# M707C.net
KiCad netlist of a schematic drawn in EAGLE
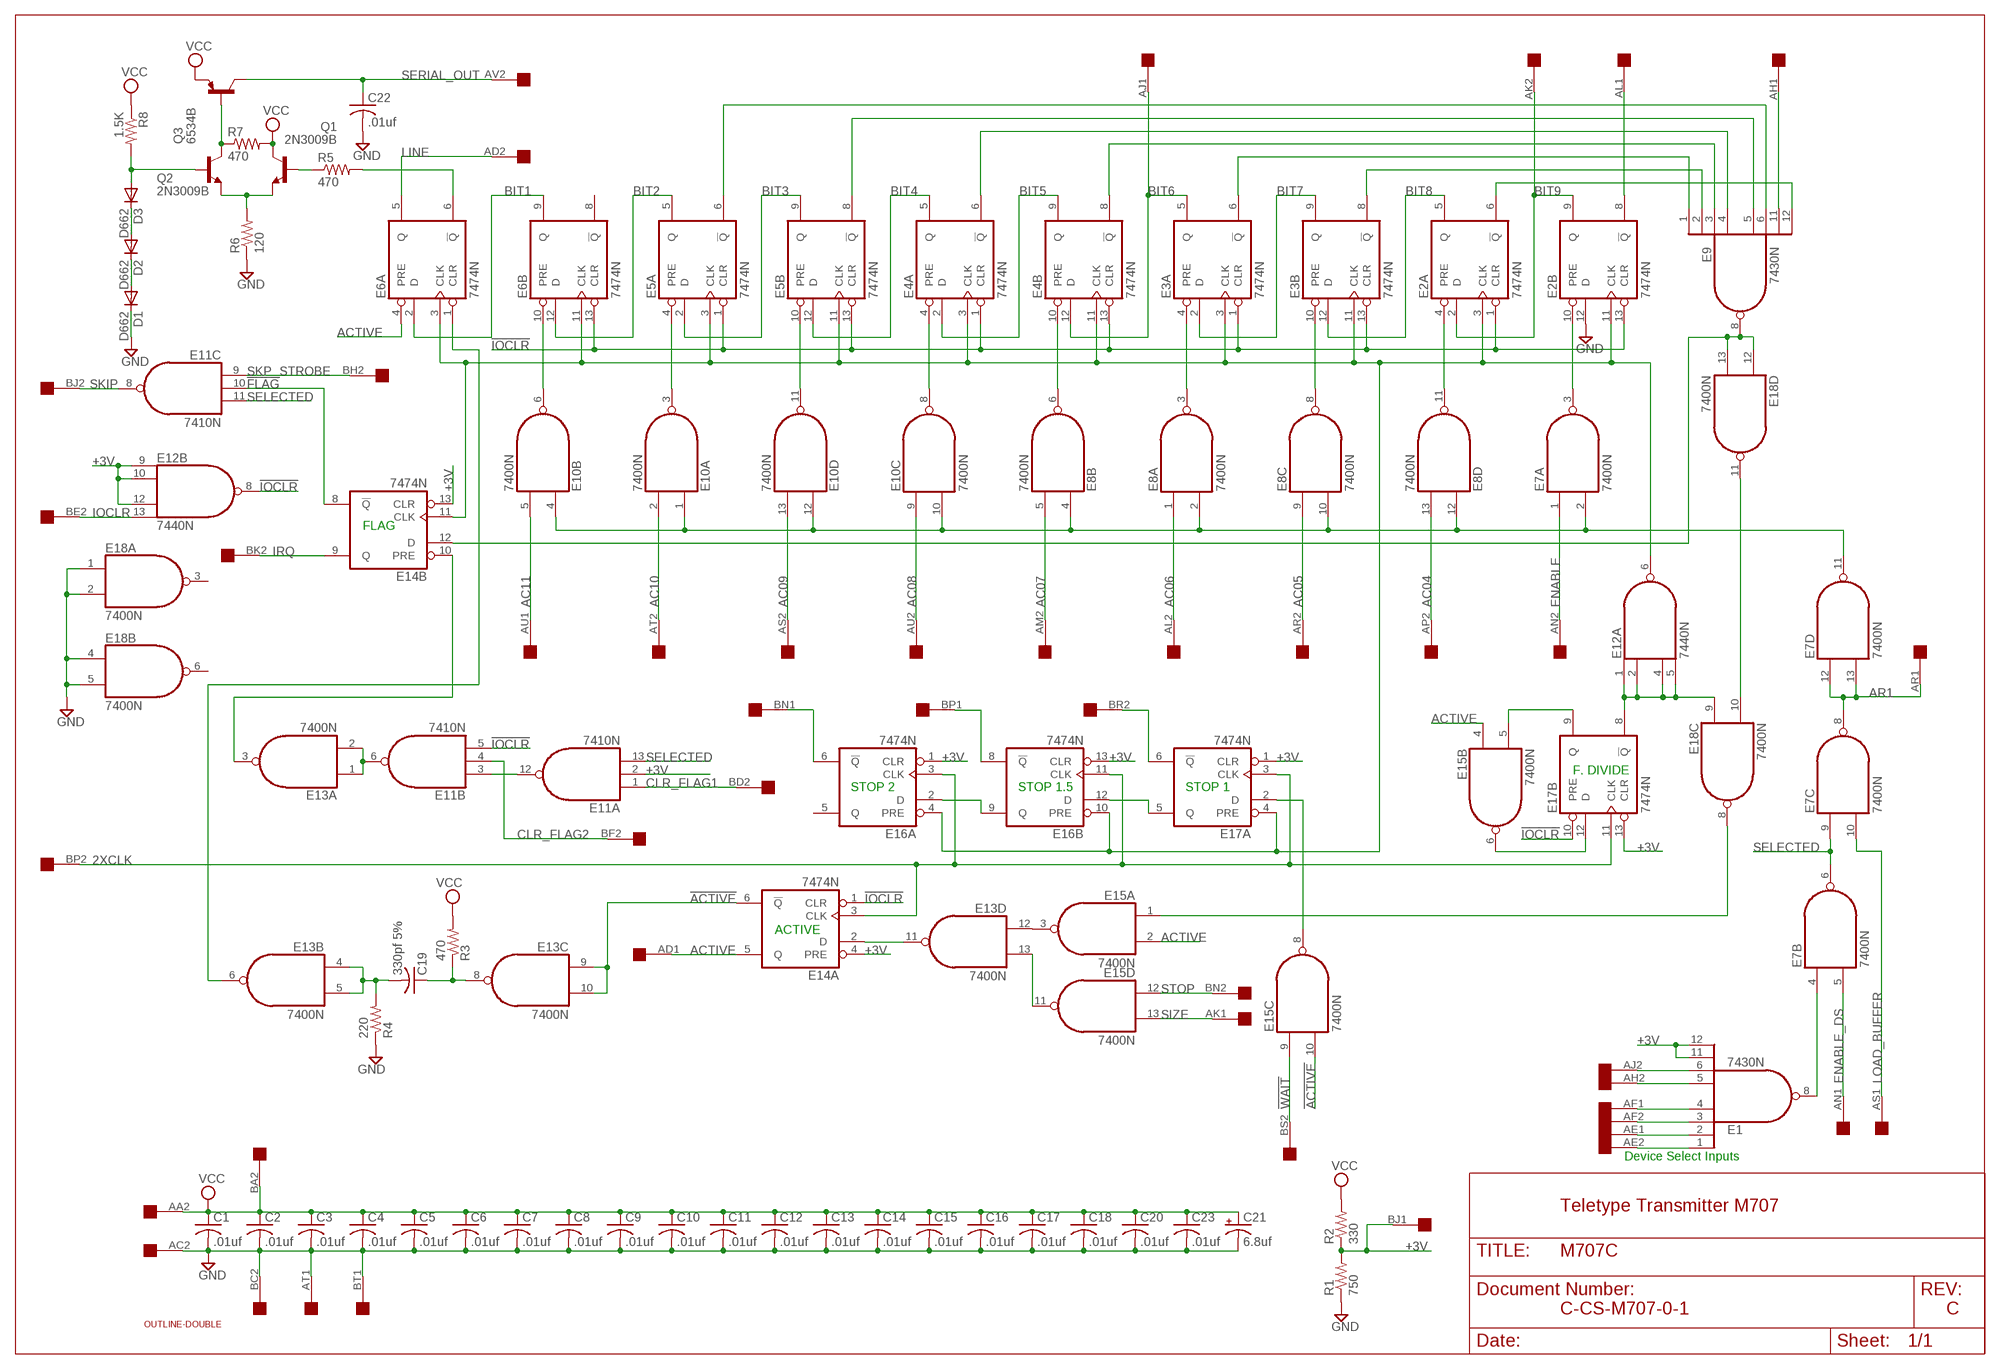
[diagram p0: schematic, sheet 1]

(export (version "E")
  (design (tool "Eeschema 10.0.6"))
  (components
    (comp (ref "C1")
      (value ".01uf")
      (footprint "eagle-import:C075-032X103")
      (libsource (lib "eagle-import") (part "C-US075-032X103"))
    )
    (comp (ref "C2")
      (value ".01uf")
      (footprint "eagle-import:C075-032X103")
      (libsource (lib "eagle-import") (part "C-US075-032X103"))
    )
    (comp (ref "C3")
      (value ".01uf")
      (footprint "eagle-import:C075-032X103")
      (libsource (lib "eagle-import") (part "C-US075-032X103"))
    )
    (comp (ref "C4")
      (value ".01uf")
      (footprint "eagle-import:C075-032X103")
      (libsource (lib "eagle-import") (part "C-US075-032X103"))
    )
    (comp (ref "C5")
      (value ".01uf")
      (footprint "eagle-import:C075-032X103")
      (libsource (lib "eagle-import") (part "C-US075-032X103"))
    )
    (comp (ref "C6")
      (value ".01uf")
      (footprint "eagle-import:C075-032X103")
      (libsource (lib "eagle-import") (part "C-US075-032X103"))
    )
    (comp (ref "C7")
      (value ".01uf")
      (footprint "eagle-import:C075-032X103")
      (libsource (lib "eagle-import") (part "C-US075-032X103"))
    )
    (comp (ref "C8")
      (value ".01uf")
      (footprint "eagle-import:C075-032X103")
      (libsource (lib "eagle-import") (part "C-US075-032X103"))
    )
    (comp (ref "C9")
      (value ".01uf")
      (footprint "eagle-import:C075-032X103")
      (libsource (lib "eagle-import") (part "C-US075-032X103"))
    )
    (comp (ref "C10")
      (value ".01uf")
      (footprint "eagle-import:C075-032X103")
      (libsource (lib "eagle-import") (part "C-US075-032X103"))
    )
    (comp (ref "C11")
      (value ".01uf")
      (footprint "eagle-import:C075-032X103")
      (libsource (lib "eagle-import") (part "C-US075-032X103"))
    )
    (comp (ref "C12")
      (value ".01uf")
      (footprint "eagle-import:C075-032X103")
      (libsource (lib "eagle-import") (part "C-US075-032X103"))
    )
    (comp (ref "C13")
      (value ".01uf")
      (footprint "eagle-import:C075-032X103")
      (libsource (lib "eagle-import") (part "C-US075-032X103"))
    )
    (comp (ref "C14")
      (value ".01uf")
      (footprint "eagle-import:C075-032X103")
      (libsource (lib "eagle-import") (part "C-US075-032X103"))
    )
    (comp (ref "C15")
      (value ".01uf")
      (footprint "eagle-import:C075-032X103")
      (libsource (lib "eagle-import") (part "C-US075-032X103"))
    )
    (comp (ref "C16")
      (value ".01uf")
      (footprint "eagle-import:C075-032X103")
      (libsource (lib "eagle-import") (part "C-US075-032X103"))
    )
    (comp (ref "C17")
      (value ".01uf")
      (footprint "eagle-import:C075-032X103")
      (libsource (lib "eagle-import") (part "C-US075-032X103"))
    )
    (comp (ref "C18")
      (value ".01uf")
      (footprint "eagle-import:C075-032X103")
      (libsource (lib "eagle-import") (part "C-US075-032X103"))
    )
    (comp (ref "C19")
      (value "330pf 5%")
      (footprint "eagle-import:C150-054X183")
      (libsource (lib "eagle-import") (part "C-US150-054X183"))
    )
    (comp (ref "C20")
      (value ".01uf")
      (footprint "eagle-import:C075-032X103")
      (libsource (lib "eagle-import") (part "C-US075-032X103"))
    )
    (comp (ref "C21")
      (value "6.8uf")
      (footprint "eagle-import:E15-5")
      (libsource (lib "eagle-import") (part "CPOL-USE15-5AXIAL"))
    )
    (comp (ref "C22")
      (value ".01uf")
      (footprint "eagle-import:C075-032X103")
      (libsource (lib "eagle-import") (part "C-US075-032X103"))
    )
    (comp (ref "C23")
      (value ".01uf")
      (footprint "eagle-import:C075-032X103")
      (libsource (lib "eagle-import") (part "C-US075-032X103"))
    )
    (comp (ref "D1")
      (value "D662")
      (footprint "eagle-import:SOD61B")
      (libsource (lib "eagle-import") (part "BY609"))
    )
    (comp (ref "D2")
      (value "D662")
      (footprint "eagle-import:SOD61B")
      (libsource (lib "eagle-import") (part "BY609"))
    )
    (comp (ref "D3")
      (value "D662")
      (footprint "eagle-import:SOD61B")
      (libsource (lib "eagle-import") (part "BY609"))
    )
    (comp (ref "E1")
      (value "7430N")
      (footprint "eagle-import:DIL14")
      (libsource (lib "eagle-import") (part "7430N"))
    )
    (comp (ref "E2")
      (value "7474N")
      (footprint "eagle-import:DIL14")
      (libsource (lib "eagle-import") (part "7474NS"))
    )
    (comp (ref "E3")
      (value "7474N")
      (footprint "eagle-import:DIL14")
      (libsource (lib "eagle-import") (part "7474NS"))
    )
    (comp (ref "E4")
      (value "7474N")
      (footprint "eagle-import:DIL14")
      (libsource (lib "eagle-import") (part "7474NS"))
    )
    (comp (ref "E5")
      (value "7474N")
      (footprint "eagle-import:DIL14")
      (libsource (lib "eagle-import") (part "7474NS"))
    )
    (comp (ref "E6")
      (value "7474N")
      (footprint "eagle-import:DIL14")
      (libsource (lib "eagle-import") (part "7474NS"))
    )
    (comp (ref "E7")
      (value "7400N")
      (footprint "eagle-import:DIL14")
      (libsource (lib "eagle-import") (part "7400N"))
    )
    (comp (ref "E8")
      (value "7400N")
      (footprint "eagle-import:DIL14")
      (libsource (lib "eagle-import") (part "7400N"))
    )
    (comp (ref "E9")
      (value "7430N")
      (footprint "eagle-import:DIL14")
      (libsource (lib "eagle-import") (part "7430N"))
    )
    (comp (ref "E10")
      (value "7400N")
      (footprint "eagle-import:DIL14")
      (libsource (lib "eagle-import") (part "7400N"))
    )
    (comp (ref "E11")
      (value "7410N")
      (footprint "eagle-import:DIL14")
      (libsource (lib "eagle-import") (part "7410N"))
    )
    (comp (ref "E12")
      (value "7440N")
      (footprint "eagle-import:DIL14")
      (libsource (lib "eagle-import") (part "7420NS"))
    )
    (comp (ref "E13")
      (value "7400N")
      (footprint "eagle-import:DIL14")
      (libsource (lib "eagle-import") (part "7400N"))
    )
    (comp (ref "E14")
      (value "7474N")
      (footprint "eagle-import:DIL14")
      (libsource (lib "eagle-import") (part "7474NS"))
    )
    (comp (ref "E15")
      (value "7400N")
      (footprint "eagle-import:DIL14")
      (libsource (lib "eagle-import") (part "7400N"))
    )
    (comp (ref "E16")
      (value "7474N")
      (footprint "eagle-import:DIL14")
      (libsource (lib "eagle-import") (part "7474NS"))
    )
    (comp (ref "E17")
      (value "7474N")
      (footprint "eagle-import:DIL14")
      (libsource (lib "eagle-import") (part "7474NS"))
    )
    (comp (ref "E18")
      (value "7400N")
      (footprint "eagle-import:DIL14")
      (libsource (lib "eagle-import") (part "7400N"))
    )
    (comp (ref "Q1")
      (value "2N3009B")
      (footprint "eagle-import:TO92-CBE")
      (libsource (lib "eagle-import") (part "-NPN-TO92-CBE2N4124"))
    )
    (comp (ref "Q2")
      (value "2N3009B")
      (footprint "eagle-import:TO92-CBE")
      (libsource (lib "eagle-import") (part "-NPN-TO92-CBE2N4124"))
    )
    (comp (ref "Q3")
      (value "6534B")
      (footprint "eagle-import:TO92-CBE")
      (libsource (lib "eagle-import") (part "-PNP-TO92-CBE2N4126"))
    )
    (comp (ref "R1")
      (value "750")
      (footprint "eagle-import:0207_15")
      (libsource (lib "eagle-import") (part "R-US_0207/15"))
    )
    (comp (ref "R2")
      (value "330")
      (footprint "eagle-import:0207_15")
      (libsource (lib "eagle-import") (part "R-US_0207/15"))
    )
    (comp (ref "R3")
      (value "470")
      (footprint "eagle-import:0207_10")
      (libsource (lib "eagle-import") (part "R-US_0207/10"))
    )
    (comp (ref "R4")
      (value "220")
      (footprint "eagle-import:0207_10")
      (libsource (lib "eagle-import") (part "R-US_0207/10"))
    )
    (comp (ref "R5")
      (value "470")
      (footprint "eagle-import:0207_10")
      (libsource (lib "eagle-import") (part "R-US_0207/10"))
    )
    (comp (ref "R6")
      (value "120")
      (footprint "eagle-import:0207_15")
      (libsource (lib "eagle-import") (part "R-US_0207/15"))
    )
    (comp (ref "R7")
      (value "470")
      (footprint "eagle-import:0207_10")
      (libsource (lib "eagle-import") (part "R-US_0207/10"))
    )
    (comp (ref "R8")
      (value "1.5K")
      (footprint "eagle-import:0207_15")
      (libsource (lib "eagle-import") (part "R-US_0207/15"))
    )
    (comp (ref "U$1")
      (value "OUTLINE-DOUBLE")
      (footprint "eagle-import:DOUBLE")
      (libsource (lib "eagle-import") (part "OUTLINE-DOUBLE"))
    )
    (comp (ref "U$2")
      (value "DOUBLE")
      (footprint "eagle-import:EDGE-CON4")
      (libsource (lib "eagle-import") (part "DOUBLE"))
    )
  )
  (nets
    (net (code "1") (name "/+3V") (class "Default")
      (node (ref "E1") (pin "11") (pinfunction "I6_11") (pintype "input"))
      (node (ref "E1") (pin "12") (pinfunction "I7_12") (pintype "input"))
      (node (ref "E11") (pin "2") (pinfunction "I1_2") (pintype "input"))
      (node (ref "E12") (pin "10") (pinfunction "I1_10") (pintype "input"))
      (node (ref "E12") (pin "12") (pinfunction "I2_12") (pintype "input"))
      (node (ref "E12") (pin "9") (pinfunction "I0_9") (pintype "input"))
      (node (ref "E14") (pin "13") (pinfunction "CLR_13") (pintype "input"))
      (node (ref "E14") (pin "4") (pinfunction "PRE_4") (pintype "input"))
      (node (ref "E16") (pin "1") (pinfunction "CLR_1") (pintype "input"))
      (node (ref "E16") (pin "13") (pinfunction "CLR_13") (pintype "input"))
      (node (ref "E17") (pin "1") (pinfunction "CLR_1") (pintype "input"))
      (node (ref "E17") (pin "13") (pinfunction "CLR_13") (pintype "input"))
      (node (ref "R1") (pin "2") (pinfunction "2_2") (pintype "passive"))
      (node (ref "R2") (pin "1") (pinfunction "1_1") (pintype "passive"))
      (node (ref "U$2") (pin "BJ1") (pinfunction "1_BJ1") (pintype "bidirectional"))
    )
    (net (code "2") (name "/2XCLK") (class "Default")
      (node (ref "E14") (pin "3") (pinfunction "CLK_3") (pintype "input"))
      (node (ref "E16") (pin "11") (pinfunction "CLK_11") (pintype "input"))
      (node (ref "E16") (pin "3") (pinfunction "CLK_3") (pintype "input"))
      (node (ref "E17") (pin "11") (pinfunction "CLK_11") (pintype "input"))
      (node (ref "E17") (pin "3") (pinfunction "CLK_3") (pintype "input"))
      (node (ref "U$2") (pin "BP2") (pinfunction "1_BP2") (pintype "bidirectional"))
    )
    (net (code "3") (name "/AC04") (class "Default")
      (node (ref "E8") (pin "13") (pinfunction "I1_13") (pintype "input"))
      (node (ref "U$2") (pin "AP2") (pinfunction "1_AP2") (pintype "bidirectional"))
    )
    (net (code "4") (name "/AC05") (class "Default")
      (node (ref "E8") (pin "9") (pinfunction "I0_9") (pintype "input"))
      (node (ref "U$2") (pin "AR2") (pinfunction "1_AR2") (pintype "bidirectional"))
    )
    (net (code "5") (name "/AC06") (class "Default")
      (node (ref "E8") (pin "1") (pinfunction "I0_1") (pintype "input"))
      (node (ref "U$2") (pin "AL2") (pinfunction "1_AL2") (pintype "bidirectional"))
    )
    (net (code "6") (name "/AC07") (class "Default")
      (node (ref "E8") (pin "5") (pinfunction "I1_5") (pintype "input"))
      (node (ref "U$2") (pin "AM2") (pinfunction "1_AM2") (pintype "bidirectional"))
    )
    (net (code "7") (name "/AC08") (class "Default")
      (node (ref "E10") (pin "9") (pinfunction "I0_9") (pintype "input"))
      (node (ref "U$2") (pin "AU2") (pinfunction "1_AU2") (pintype "bidirectional"))
    )
    (net (code "8") (name "/AC09") (class "Default")
      (node (ref "E10") (pin "13") (pinfunction "I1_13") (pintype "input"))
      (node (ref "U$2") (pin "AS2") (pinfunction "1_AS2") (pintype "bidirectional"))
    )
    (net (code "9") (name "/AC10") (class "Default")
      (node (ref "E10") (pin "2") (pinfunction "I1_2") (pintype "input"))
      (node (ref "U$2") (pin "AT2") (pinfunction "1_AT2") (pintype "bidirectional"))
    )
    (net (code "10") (name "/AC11") (class "Default")
      (node (ref "E10") (pin "5") (pinfunction "I1_5") (pintype "input"))
      (node (ref "U$2") (pin "AU1") (pinfunction "1_AU1") (pintype "bidirectional"))
    )
    (net (code "11") (name "/ACTIVE") (class "Default")
      (node (ref "E14") (pin "5") (pinfunction "Q_5") (pintype "output"))
      (node (ref "E15") (pin "2") (pinfunction "I1_2") (pintype "input"))
      (node (ref "E15") (pin "4") (pinfunction "I0_4") (pintype "input"))
      (node (ref "E6") (pin "4") (pinfunction "PRE_4") (pintype "input"))
      (node (ref "U$2") (pin "AD1") (pinfunction "1_AD1") (pintype "bidirectional"))
    )
    (net (code "12") (name "/AR1") (class "Default")
      (node (ref "E7") (pin "12") (pinfunction "I0_12") (pintype "input"))
      (node (ref "E7") (pin "13") (pinfunction "I1_13") (pintype "input"))
      (node (ref "E7") (pin "8") (pinfunction "O_8") (pintype "output"))
      (node (ref "U$2") (pin "AR1") (pinfunction "1_AR1") (pintype "bidirectional"))
    )
    (net (code "13") (name "/BIT1") (class "Default")
      (node (ref "E6") (pin "2") (pinfunction "D_2") (pintype "input"))
      (node (ref "E6") (pin "9") (pinfunction "Q_9") (pintype "output"))
    )
    (net (code "14") (name "/BIT2") (class "Default")
      (node (ref "E5") (pin "5") (pinfunction "Q_5") (pintype "output"))
      (node (ref "E6") (pin "12") (pinfunction "D_12") (pintype "input"))
    )
    (net (code "15") (name "/BIT3") (class "Default")
      (node (ref "E5") (pin "2") (pinfunction "D_2") (pintype "input"))
      (node (ref "E5") (pin "9") (pinfunction "Q_9") (pintype "output"))
    )
    (net (code "16") (name "/BIT4") (class "Default")
      (node (ref "E4") (pin "5") (pinfunction "Q_5") (pintype "output"))
      (node (ref "E5") (pin "12") (pinfunction "D_12") (pintype "input"))
    )
    (net (code "17") (name "/BIT5") (class "Default")
      (node (ref "E4") (pin "2") (pinfunction "D_2") (pintype "input"))
      (node (ref "E4") (pin "9") (pinfunction "Q_9") (pintype "output"))
    )
    (net (code "18") (name "/BIT6") (class "Default")
      (node (ref "E3") (pin "5") (pinfunction "Q_5") (pintype "output"))
      (node (ref "E4") (pin "12") (pinfunction "D_12") (pintype "input"))
      (node (ref "U$2") (pin "AJ1") (pinfunction "1_AJ1") (pintype "bidirectional"))
    )
    (net (code "19") (name "/BIT7") (class "Default")
      (node (ref "E3") (pin "2") (pinfunction "D_2") (pintype "input"))
      (node (ref "E3") (pin "9") (pinfunction "Q_9") (pintype "output"))
    )
    (net (code "20") (name "/BIT8") (class "Default")
      (node (ref "E2") (pin "5") (pinfunction "Q_5") (pintype "output"))
      (node (ref "E3") (pin "12") (pinfunction "D_12") (pintype "input"))
    )
    (net (code "21") (name "/BIT9") (class "Default")
      (node (ref "E2") (pin "2") (pinfunction "D_2") (pintype "input"))
      (node (ref "E2") (pin "9") (pinfunction "Q_9") (pintype "output"))
      (node (ref "U$2") (pin "AK2") (pinfunction "1_AK2") (pintype "bidirectional"))
    )
    (net (code "22") (name "/CLR_FLAG1") (class "Default")
      (node (ref "E11") (pin "1") (pinfunction "I0_1") (pintype "input"))
      (node (ref "U$2") (pin "BD2") (pinfunction "1_BD2") (pintype "bidirectional"))
    )
    (net (code "23") (name "/CLR_FLAG2") (class "Default")
      (node (ref "E11") (pin "4") (pinfunction "I1_4") (pintype "input"))
      (node (ref "U$2") (pin "BF2") (pinfunction "1_BF2") (pintype "bidirectional"))
    )
    (net (code "24") (name "/ENABLE") (class "Default")
      (node (ref "E7") (pin "1") (pinfunction "I0_1") (pintype "input"))
      (node (ref "U$2") (pin "AN2") (pinfunction "1_AN2") (pintype "bidirectional"))
    )
    (net (code "25") (name "/ENABLE_DS") (class "Default")
      (node (ref "E7") (pin "5") (pinfunction "I1_5") (pintype "input"))
      (node (ref "U$2") (pin "AN1") (pinfunction "1_AN1") (pintype "bidirectional"))
    )
    (net (code "26") (name "/IOCLR") (class "Default")
      (node (ref "E12") (pin "13") (pinfunction "I3_13") (pintype "input"))
      (node (ref "U$2") (pin "BE2") (pinfunction "1_BE2") (pintype "bidirectional"))
    )
    (net (code "27") (name "/IRQ") (class "Default")
      (node (ref "E14") (pin "9") (pinfunction "Q_9") (pintype "output"))
      (node (ref "U$2") (pin "BK2") (pinfunction "1_BK2") (pintype "bidirectional"))
    )
    (net (code "28") (name "/LINE") (class "Default")
      (node (ref "E6") (pin "5") (pinfunction "Q_5") (pintype "output"))
      (node (ref "U$2") (pin "AD2") (pinfunction "1_AD2") (pintype "bidirectional"))
    )
    (net (code "29") (name "/LOAD_BUFFER") (class "Default")
      (node (ref "E7") (pin "10") (pinfunction "I1_10") (pintype "input"))
      (node (ref "U$2") (pin "AS1") (pinfunction "1_AS1") (pintype "bidirectional"))
    )
    (net (code "30") (name "/SELECTED") (class "Default")
      (node (ref "E11") (pin "11") (pinfunction "I2_11") (pintype "input"))
      (node (ref "E11") (pin "13") (pinfunction "I2_13") (pintype "input"))
      (node (ref "E7") (pin "6") (pinfunction "O_6") (pintype "output"))
      (node (ref "E7") (pin "9") (pinfunction "I0_9") (pintype "input"))
    )
    (net (code "31") (name "/SERIAL_OUT") (class "Default")
      (node (ref "C22") (pin "1") (pinfunction "1_1") (pintype "passive"))
      (node (ref "Q3") (pin "C") (pinfunction "C_C") (pintype "passive"))
      (node (ref "U$2") (pin "AV2") (pinfunction "1_AV2") (pintype "bidirectional"))
    )
    (net (code "32") (name "/SIZE") (class "Default")
      (node (ref "E15") (pin "13") (pinfunction "I1_13") (pintype "input"))
      (node (ref "U$2") (pin "AK1") (pinfunction "1_AK1") (pintype "bidirectional"))
    )
    (net (code "33") (name "/SKIP") (class "Default")
      (node (ref "E11") (pin "8") (pinfunction "O_8") (pintype "output"))
      (node (ref "U$2") (pin "BJ2") (pinfunction "1_BJ2") (pintype "bidirectional"))
    )
    (net (code "34") (name "/SKP_STROBE") (class "Default")
      (node (ref "E11") (pin "9") (pinfunction "I0_9") (pintype "input"))
      (node (ref "U$2") (pin "BH2") (pinfunction "1_BH2") (pintype "bidirectional"))
    )
    (net (code "35") (name "/STOP") (class "Default")
      (node (ref "E15") (pin "12") (pinfunction "I0_12") (pintype "input"))
      (node (ref "U$2") (pin "BN2") (pinfunction "1_BN2") (pintype "bidirectional"))
    )
    (net (code "36") (name "/~{ACTIVE}") (class "Default")
      (node (ref "E13") (pin "10") (pinfunction "I1_10") (pintype "input"))
      (node (ref "E13") (pin "9") (pinfunction "I0_9") (pintype "input"))
      (node (ref "E14") (pin "6") (pinfunction "~{Q}_6") (pintype "output"))
      (node (ref "E15") (pin "10") (pinfunction "I1_10") (pintype "input"))
    )
    (net (code "37") (name "/~{FLAG}") (class "Default")
      (node (ref "E11") (pin "10") (pinfunction "I1_10") (pintype "input"))
      (node (ref "E14") (pin "8") (pinfunction "~{Q}_8") (pintype "output"))
    )
    (net (code "38") (name "/~{IOCLR}") (class "Default")
      (node (ref "E11") (pin "5") (pinfunction "I2_5") (pintype "input"))
      (node (ref "E12") (pin "8") (pinfunction "O_8") (pintype "output"))
      (node (ref "E14") (pin "1") (pinfunction "CLR_1") (pintype "input"))
      (node (ref "E17") (pin "10") (pinfunction "PRE_10") (pintype "input"))
      (node (ref "E2") (pin "1") (pinfunction "CLR_1") (pintype "input"))
      (node (ref "E2") (pin "13") (pinfunction "CLR_13") (pintype "input"))
      (node (ref "E3") (pin "1") (pinfunction "CLR_1") (pintype "input"))
      (node (ref "E3") (pin "13") (pinfunction "CLR_13") (pintype "input"))
      (node (ref "E4") (pin "1") (pinfunction "CLR_1") (pintype "input"))
      (node (ref "E4") (pin "13") (pinfunction "CLR_13") (pintype "input"))
      (node (ref "E5") (pin "1") (pinfunction "CLR_1") (pintype "input"))
      (node (ref "E5") (pin "13") (pinfunction "CLR_13") (pintype "input"))
      (node (ref "E6") (pin "13") (pinfunction "CLR_13") (pintype "input"))
    )
    (net (code "39") (name "/~{WAIT}") (class "Default")
      (node (ref "E15") (pin "9") (pinfunction "I0_9") (pintype "input"))
      (node (ref "U$2") (pin "BS2") (pinfunction "1_BS2") (pintype "bidirectional"))
    )
    (net (code "40") (name "GND") (class "Default")
      (node (ref "C1") (pin "2") (pinfunction "2_2") (pintype "passive"))
      (node (ref "C10") (pin "2") (pinfunction "2_2") (pintype "passive"))
      (node (ref "C11") (pin "2") (pinfunction "2_2") (pintype "passive"))
      (node (ref "C12") (pin "2") (pinfunction "2_2") (pintype "passive"))
      (node (ref "C13") (pin "2") (pinfunction "2_2") (pintype "passive"))
      (node (ref "C14") (pin "2") (pinfunction "2_2") (pintype "passive"))
      (node (ref "C15") (pin "2") (pinfunction "2_2") (pintype "passive"))
      (node (ref "C16") (pin "2") (pinfunction "2_2") (pintype "passive"))
      (node (ref "C17") (pin "2") (pinfunction "2_2") (pintype "passive"))
      (node (ref "C18") (pin "2") (pinfunction "2_2") (pintype "passive"))
      (node (ref "C2") (pin "2") (pinfunction "2_2") (pintype "passive"))
      (node (ref "C20") (pin "2") (pinfunction "2_2") (pintype "passive"))
      (node (ref "C21") (pin "-") (pinfunction "-_-") (pintype "passive"))
      (node (ref "C22") (pin "2") (pinfunction "2_2") (pintype "passive"))
      (node (ref "C23") (pin "2") (pinfunction "2_2") (pintype "passive"))
      (node (ref "C3") (pin "2") (pinfunction "2_2") (pintype "passive"))
      (node (ref "C4") (pin "2") (pinfunction "2_2") (pintype "passive"))
      (node (ref "C5") (pin "2") (pinfunction "2_2") (pintype "passive"))
      (node (ref "C6") (pin "2") (pinfunction "2_2") (pintype "passive"))
      (node (ref "C7") (pin "2") (pinfunction "2_2") (pintype "passive"))
      (node (ref "C8") (pin "2") (pinfunction "2_2") (pintype "passive"))
      (node (ref "C9") (pin "2") (pinfunction "2_2") (pintype "passive"))
      (node (ref "D1") (pin "C") (pinfunction "C_C") (pintype "passive"))
      (node (ref "E18") (pin "1") (pinfunction "I0_1") (pintype "input"))
      (node (ref "E18") (pin "2") (pinfunction "I1_2") (pintype "input"))
      (node (ref "E18") (pin "4") (pinfunction "I0_4") (pintype "input"))
      (node (ref "E18") (pin "5") (pinfunction "I1_5") (pintype "input"))
      (node (ref "E2") (pin "12") (pinfunction "D_12") (pintype "input"))
      (node (ref "R1") (pin "1") (pinfunction "1_1") (pintype "passive"))
      (node (ref "R4") (pin "1") (pinfunction "1_1") (pintype "passive"))
      (node (ref "R6") (pin "1") (pinfunction "1_1") (pintype "passive"))
      (node (ref "U$2") (pin "AC2") (pinfunction "1_AC2") (pintype "bidirectional"))
      (node (ref "U$2") (pin "AT1") (pinfunction "1_AT1") (pintype "bidirectional"))
      (node (ref "U$2") (pin "BC2") (pinfunction "1_BC2") (pintype "bidirectional"))
      (node (ref "U$2") (pin "BT1") (pinfunction "1_BT1") (pintype "bidirectional"))
    )
    (net (code "41") (name "Net-(D1-PadA)") (class "Default")
      (node (ref "D1") (pin "A") (pinfunction "A_A") (pintype "passive"))
      (node (ref "D2") (pin "C") (pinfunction "C_C") (pintype "passive"))
    )
    (net (code "42") (name "Net-(D2-PadA)") (class "Default")
      (node (ref "D2") (pin "A") (pinfunction "A_A") (pintype "passive"))
      (node (ref "D3") (pin "C") (pinfunction "C_C") (pintype "passive"))
    )
    (net (code "43") (name "Net-(D3-PadA)") (class "Default")
      (node (ref "D3") (pin "A") (pinfunction "A_A") (pintype "passive"))
      (node (ref "Q2") (pin "B") (pinfunction "B_B") (pintype "passive"))
      (node (ref "R8") (pin "2") (pinfunction "2_2") (pintype "passive"))
    )
    (net (code "44") (name "Net-(E1A-I0)") (class "Default")
      (node (ref "E1") (pin "1") (pinfunction "I0_1") (pintype "input"))
      (node (ref "U$2") (pin "AE2") (pinfunction "1_AE2") (pintype "bidirectional"))
    )
    (net (code "45") (name "Net-(E1A-I1)") (class "Default")
      (node (ref "E1") (pin "2") (pinfunction "I1_2") (pintype "input"))
      (node (ref "U$2") (pin "AE1") (pinfunction "1_AE1") (pintype "bidirectional"))
    )
    (net (code "46") (name "Net-(E1A-I2)") (class "Default")
      (node (ref "E1") (pin "3") (pinfunction "I2_3") (pintype "input"))
      (node (ref "U$2") (pin "AF2") (pinfunction "1_AF2") (pintype "bidirectional"))
    )
    (net (code "47") (name "Net-(E1A-I3)") (class "Default")
      (node (ref "E1") (pin "4") (pinfunction "I3_4") (pintype "input"))
      (node (ref "U$2") (pin "AF1") (pinfunction "1_AF1") (pintype "bidirectional"))
    )
    (net (code "48") (name "Net-(E1A-I4)") (class "Default")
      (node (ref "E1") (pin "5") (pinfunction "I4_5") (pintype "input"))
      (node (ref "U$2") (pin "AH2") (pinfunction "1_AH2") (pintype "bidirectional"))
    )
    (net (code "49") (name "Net-(E1A-I5)") (class "Default")
      (node (ref "E1") (pin "6") (pinfunction "I5_6") (pintype "input"))
      (node (ref "U$2") (pin "AJ2") (pinfunction "1_AJ2") (pintype "bidirectional"))
    )
    (net (code "50") (name "Net-(E1A-O)") (class "Default")
      (node (ref "E1") (pin "8") (pinfunction "O_8") (pintype "output"))
      (node (ref "E7") (pin "4") (pinfunction "I0_4") (pintype "input"))
    )
    (net (code "51") (name "Net-(E2A-PRE)") (class "Default")
      (node (ref "E2") (pin "4") (pinfunction "PRE_4") (pintype "input"))
      (node (ref "E8") (pin "11") (pinfunction "O_11") (pintype "output"))
    )
    (net (code "52") (name "Net-(E2A-~{Q})") (class "Default")
      (node (ref "E2") (pin "6") (pinfunction "~{Q}_6") (pintype "output"))
      (node (ref "E9") (pin "12") (pinfunction "I7_12") (pintype "input"))
    )
    (net (code "53") (name "Net-(E2B-PRE)") (class "Default")
      (node (ref "E2") (pin "10") (pinfunction "PRE_10") (pintype "input"))
      (node (ref "E7") (pin "3") (pinfunction "O_3") (pintype "output"))
    )
    (net (code "54") (name "Net-(E2B-~{Q})") (class "Default")
      (node (ref "E2") (pin "8") (pinfunction "~{Q}_8") (pintype "output"))
      (node (ref "U$2") (pin "AL1") (pinfunction "1_AL1") (pintype "bidirectional"))
    )
    (net (code "55") (name "Net-(E3A-PRE)") (class "Default")
      (node (ref "E3") (pin "4") (pinfunction "PRE_4") (pintype "input"))
      (node (ref "E8") (pin "3") (pinfunction "O_3") (pintype "output"))
    )
    (net (code "56") (name "Net-(E3A-~{Q})") (class "Default")
      (node (ref "E3") (pin "6") (pinfunction "~{Q}_6") (pintype "output"))
      (node (ref "E9") (pin "1") (pinfunction "I0_1") (pintype "input"))
    )
    (net (code "57") (name "Net-(E3B-PRE)") (class "Default")
      (node (ref "E3") (pin "10") (pinfunction "PRE_10") (pintype "input"))
      (node (ref "E8") (pin "8") (pinfunction "O_8") (pintype "output"))
    )
    (net (code "58") (name "Net-(E3B-~{Q})") (class "Default")
      (node (ref "E3") (pin "8") (pinfunction "~{Q}_8") (pintype "output"))
      (node (ref "E9") (pin "2") (pinfunction "I1_2") (pintype "input"))
    )
    (net (code "59") (name "Net-(E4A-~{Q})") (class "Default")
      (node (ref "E4") (pin "6") (pinfunction "~{Q}_6") (pintype "output"))
      (node (ref "E9") (pin "4") (pinfunction "I3_4") (pintype "input"))
    )
    (net (code "60") (name "Net-(E4B-PRE)") (class "Default")
      (node (ref "E4") (pin "10") (pinfunction "PRE_10") (pintype "input"))
      (node (ref "E8") (pin "6") (pinfunction "O_6") (pintype "output"))
    )
    (net (code "61") (name "Net-(E4B-~{Q})") (class "Default")
      (node (ref "E4") (pin "8") (pinfunction "~{Q}_8") (pintype "output"))
      (node (ref "E9") (pin "3") (pinfunction "I2_3") (pintype "input"))
    )
    (net (code "62") (name "Net-(E5A-~{Q})") (class "Default")
      (node (ref "E5") (pin "6") (pinfunction "~{Q}_6") (pintype "output"))
      (node (ref "E9") (pin "6") (pinfunction "I5_6") (pintype "input"))
    )
    (net (code "63") (name "Net-(E5B-~{Q})") (class "Default")
      (node (ref "E5") (pin "8") (pinfunction "~{Q}_8") (pintype "output"))
      (node (ref "E9") (pin "5") (pinfunction "I4_5") (pintype "input"))
    )
    (net (code "64") (name "Net-(E6A-~{Q})") (class "Default")
      (node (ref "E6") (pin "6") (pinfunction "~{Q}_6") (pintype "output"))
      (node (ref "R5") (pin "2") (pinfunction "2_2") (pintype "passive"))
    )
    (net (code "65") (name "Net-(E9A-I6)") (class "Default")
      (node (ref "E9") (pin "11") (pinfunction "I6_11") (pintype "input"))
      (node (ref "U$2") (pin "AH1") (pinfunction "1_AH1") (pintype "bidirectional"))
    )
    (net (code "66") (name "Net-(E10A-I0)") (class "Default")
      (node (ref "E10") (pin "1") (pinfunction "I0_1") (pintype "input"))
      (node (ref "E10") (pin "10") (pinfunction "I1_10") (pintype "input"))
      (node (ref "E10") (pin "12") (pinfunction "I0_12") (pintype "input"))
      (node (ref "E10") (pin "4") (pinfunction "I0_4") (pintype "input"))
      (node (ref "E7") (pin "11") (pinfunction "O_11") (pintype "output"))
      (node (ref "E7") (pin "2") (pinfunction "I1_2") (pintype "input"))
      (node (ref "E8") (pin "10") (pinfunction "I1_10") (pintype "input"))
      (node (ref "E8") (pin "12") (pinfunction "I0_12") (pintype "input"))
      (node (ref "E8") (pin "2") (pinfunction "I1_2") (pintype "input"))
      (node (ref "E8") (pin "4") (pinfunction "I0_4") (pintype "input"))
    )
    (net (code "67") (name "Net-(E10A-O)") (class "Default")
      (node (ref "E10") (pin "3") (pinfunction "O_3") (pintype "output"))
      (node (ref "E5") (pin "4") (pinfunction "PRE_4") (pintype "input"))
    )
    (net (code "68") (name "Net-(E10B-O)") (class "Default")
      (node (ref "E10") (pin "6") (pinfunction "O_6") (pintype "output"))
      (node (ref "E6") (pin "10") (pinfunction "PRE_10") (pintype "input"))
    )
    (net (code "69") (name "Net-(E10C-O)") (class "Default")
      (node (ref "E10") (pin "8") (pinfunction "O_8") (pintype "output"))
      (node (ref "E4") (pin "4") (pinfunction "PRE_4") (pintype "input"))
    )
    (net (code "70") (name "Net-(E10D-O)") (class "Default")
      (node (ref "E10") (pin "11") (pinfunction "O_11") (pintype "output"))
      (node (ref "E5") (pin "10") (pinfunction "PRE_10") (pintype "input"))
    )
    (net (code "71") (name "Net-(E11A-O)") (class "Default")
      (node (ref "E11") (pin "12") (pinfunction "O_12") (pintype "output"))
      (node (ref "E11") (pin "3") (pinfunction "I0_3") (pintype "input"))
    )
    (net (code "72") (name "Net-(E11B-O)") (class "Default")
      (node (ref "E11") (pin "6") (pinfunction "O_6") (pintype "output"))
      (node (ref "E13") (pin "1") (pinfunction "I0_1") (pintype "input"))
      (node (ref "E13") (pin "2") (pinfunction "I1_2") (pintype "input"))
    )
    (net (code "73") (name "Net-(E12A-I0)") (class "Default")
      (node (ref "E12") (pin "1") (pinfunction "I0_1") (pintype "input"))
      (node (ref "E12") (pin "2") (pinfunction "I1_2") (pintype "input"))
      (node (ref "E12") (pin "4") (pinfunction "I2_4") (pintype "input"))
      (node (ref "E12") (pin "5") (pinfunction "I3_5") (pintype "input"))
      (node (ref "E17") (pin "8") (pinfunction "~{Q}_8") (pintype "output"))
      (node (ref "E18") (pin "9") (pinfunction "I0_9") (pintype "input"))
    )
    (net (code "74") (name "Net-(E12A-O)") (class "Default")
      (node (ref "E12") (pin "6") (pinfunction "O_6") (pintype "output"))
      (node (ref "E14") (pin "11") (pinfunction "CLK_11") (pintype "input"))
      (node (ref "E16") (pin "10") (pinfunction "PRE_10") (pintype "input"))
      (node (ref "E16") (pin "4") (pinfunction "PRE_4") (pintype "input"))
      (node (ref "E17") (pin "4") (pinfunction "PRE_4") (pintype "input"))
      (node (ref "E2") (pin "11") (pinfunction "CLK_11") (pintype "input"))
      (node (ref "E2") (pin "3") (pinfunction "CLK_3") (pintype "input"))
      (node (ref "E3") (pin "11") (pinfunction "CLK_11") (pintype "input"))
      (node (ref "E3") (pin "3") (pinfunction "CLK_3") (pintype "input"))
      (node (ref "E4") (pin "11") (pinfunction "CLK_11") (pintype "input"))
      (node (ref "E4") (pin "3") (pinfunction "CLK_3") (pintype "input"))
      (node (ref "E5") (pin "11") (pinfunction "CLK_11") (pintype "input"))
      (node (ref "E5") (pin "3") (pinfunction "CLK_3") (pintype "input"))
      (node (ref "E6") (pin "11") (pinfunction "CLK_11") (pintype "input"))
      (node (ref "E6") (pin "3") (pinfunction "CLK_3") (pintype "input"))
    )
    (net (code "75") (name "Net-(E13A-O)") (class "Default")
      (node (ref "E13") (pin "3") (pinfunction "O_3") (pintype "output"))
      (node (ref "E14") (pin "10") (pinfunction "PRE_10") (pintype "input"))
    )
    (net (code "76") (name "Net-(E13B-I0)") (class "Default")
      (node (ref "C19") (pin "2") (pinfunction "2_2") (pintype "passive"))
      (node (ref "E13") (pin "4") (pinfunction "I0_4") (pintype "input"))
      (node (ref "E13") (pin "5") (pinfunction "I1_5") (pintype "input"))
      (node (ref "R4") (pin "2") (pinfunction "2_2") (pintype "passive"))
    )
    (net (code "77") (name "Net-(E13B-O)") (class "Default")
      (node (ref "E13") (pin "6") (pinfunction "O_6") (pintype "output"))
      (node (ref "E6") (pin "1") (pinfunction "CLR_1") (pintype "input"))
    )
    (net (code "78") (name "Net-(E13C-O)") (class "Default")
      (node (ref "C19") (pin "1") (pinfunction "1_1") (pintype "passive"))
      (node (ref "E13") (pin "8") (pinfunction "O_8") (pintype "output"))
      (node (ref "R3") (pin "1") (pinfunction "1_1") (pintype "passive"))
    )
    (net (code "79") (name "Net-(E13D-I0)") (class "Default")
      (node (ref "E13") (pin "12") (pinfunction "I0_12") (pintype "input"))
      (node (ref "E15") (pin "3") (pinfunction "O_3") (pintype "output"))
    )
    (net (code "80") (name "Net-(E13D-I1)") (class "Default")
      (node (ref "E13") (pin "13") (pinfunction "I1_13") (pintype "input"))
      (node (ref "E15") (pin "11") (pinfunction "O_11") (pintype "output"))
    )
    (net (code "81") (name "Net-(E13D-O)") (class "Default")
      (node (ref "E13") (pin "11") (pinfunction "O_11") (pintype "output"))
      (node (ref "E14") (pin "2") (pinfunction "D_2") (pintype "input"))
    )
    (net (code "82") (name "Net-(E14B-D)") (class "Default")
      (node (ref "E14") (pin "12") (pinfunction "D_12") (pintype "input"))
      (node (ref "E18") (pin "12") (pinfunction "I0_12") (pintype "input"))
      (node (ref "E18") (pin "13") (pinfunction "I1_13") (pintype "input"))
      (node (ref "E9") (pin "8") (pinfunction "O_8") (pintype "output"))
    )
    (net (code "83") (name "Net-(E15A-I0)") (class "Default")
      (node (ref "E15") (pin "1") (pinfunction "I0_1") (pintype "input"))
      (node (ref "E18") (pin "8") (pinfunction "O_8") (pintype "output"))
    )
    (net (code "84") (name "Net-(E15B-I1)") (class "Default")
      (node (ref "E15") (pin "5") (pinfunction "I1_5") (pintype "input"))
      (node (ref "E17") (pin "9") (pinfunction "Q_9") (pintype "output"))
    )
    (net (code "85") (name "Net-(E15B-O)") (class "Default")
      (node (ref "E15") (pin "6") (pinfunction "O_6") (pintype "output"))
      (node (ref "E17") (pin "12") (pinfunction "D_12") (pintype "input"))
    )
    (net (code "86") (name "Net-(E15C-O)") (class "Default")
      (node (ref "E15") (pin "8") (pinfunction "O_8") (pintype "output"))
      (node (ref "E17") (pin "2") (pinfunction "D_2") (pintype "input"))
    )
    (net (code "87") (name "Net-(E16A-D)") (class "Default")
      (node (ref "E16") (pin "2") (pinfunction "D_2") (pintype "input"))
      (node (ref "E16") (pin "9") (pinfunction "Q_9") (pintype "output"))
    )
    (net (code "88") (name "Net-(E16A-~{Q})") (class "Default")
      (node (ref "E16") (pin "6") (pinfunction "~{Q}_6") (pintype "output"))
      (node (ref "U$2") (pin "BN1") (pinfunction "1_BN1") (pintype "bidirectional"))
    )
    (net (code "89") (name "Net-(E16B-D)") (class "Default")
      (node (ref "E16") (pin "12") (pinfunction "D_12") (pintype "input"))
      (node (ref "E17") (pin "5") (pinfunction "Q_5") (pintype "output"))
    )
    (net (code "90") (name "Net-(E16B-~{Q})") (class "Default")
      (node (ref "E16") (pin "8") (pinfunction "~{Q}_8") (pintype "output"))
      (node (ref "U$2") (pin "BP1") (pinfunction "1_BP1") (pintype "bidirectional"))
    )
    (net (code "91") (name "Net-(E17A-~{Q})") (class "Default")
      (node (ref "E17") (pin "6") (pinfunction "~{Q}_6") (pintype "output"))
      (node (ref "U$2") (pin "BR2") (pinfunction "1_BR2") (pintype "bidirectional"))
    )
    (net (code "92") (name "Net-(E18C-I1)") (class "Default")
      (node (ref "E18") (pin "10") (pinfunction "I1_10") (pintype "input"))
      (node (ref "E18") (pin "11") (pinfunction "O_11") (pintype "output"))
    )
    (net (code "93") (name "Net-(Q1-PadB)") (class "Default")
      (node (ref "Q1") (pin "B") (pinfunction "B_B") (pintype "passive"))
      (node (ref "R5") (pin "1") (pinfunction "1_1") (pintype "passive"))
    )
    (net (code "94") (name "Net-(Q1-PadE)") (class "Default")
      (node (ref "Q1") (pin "E") (pinfunction "E_E") (pintype "passive"))
      (node (ref "Q2") (pin "E") (pinfunction "E_E") (pintype "passive"))
      (node (ref "R6") (pin "2") (pinfunction "2_2") (pintype "passive"))
    )
    (net (code "95") (name "Net-(Q2-PadC)") (class "Default")
      (node (ref "Q2") (pin "C") (pinfunction "C_C") (pintype "passive"))
      (node (ref "Q3") (pin "B") (pinfunction "B_B") (pintype "passive"))
      (node (ref "R7") (pin "1") (pinfunction "1_1") (pintype "passive"))
    )
    (net (code "96") (name "VCC") (class "Default")
      (node (ref "C1") (pin "1") (pinfunction "1_1") (pintype "passive"))
      (node (ref "C10") (pin "1") (pinfunction "1_1") (pintype "passive"))
      (node (ref "C11") (pin "1") (pinfunction "1_1") (pintype "passive"))
      (node (ref "C12") (pin "1") (pinfunction "1_1") (pintype "passive"))
      (node (ref "C13") (pin "1") (pinfunction "1_1") (pintype "passive"))
      (node (ref "C14") (pin "1") (pinfunction "1_1") (pintype "passive"))
      (node (ref "C15") (pin "1") (pinfunction "1_1") (pintype "passive"))
      (node (ref "C16") (pin "1") (pinfunction "1_1") (pintype "passive"))
      (node (ref "C17") (pin "1") (pinfunction "1_1") (pintype "passive"))
      (node (ref "C18") (pin "1") (pinfunction "1_1") (pintype "passive"))
      (node (ref "C2") (pin "1") (pinfunction "1_1") (pintype "passive"))
      (node (ref "C20") (pin "1") (pinfunction "1_1") (pintype "passive"))
      (node (ref "C21") (pin "+") (pinfunction "+_+") (pintype "passive"))
      (node (ref "C23") (pin "1") (pinfunction "1_1") (pintype "passive"))
      (node (ref "C3") (pin "1") (pinfunction "1_1") (pintype "passive"))
      (node (ref "C4") (pin "1") (pinfunction "1_1") (pintype "passive"))
      (node (ref "C5") (pin "1") (pinfunction "1_1") (pintype "passive"))
      (node (ref "C6") (pin "1") (pinfunction "1_1") (pintype "passive"))
      (node (ref "C7") (pin "1") (pinfunction "1_1") (pintype "passive"))
      (node (ref "C8") (pin "1") (pinfunction "1_1") (pintype "passive"))
      (node (ref "C9") (pin "1") (pinfunction "1_1") (pintype "passive"))
      (node (ref "Q1") (pin "C") (pinfunction "C_C") (pintype "passive"))
      (node (ref "Q3") (pin "E") (pinfunction "E_E") (pintype "passive"))
      (node (ref "R2") (pin "2") (pinfunction "2_2") (pintype "passive"))
      (node (ref "R3") (pin "2") (pinfunction "2_2") (pintype "passive"))
      (node (ref "R7") (pin "2") (pinfunction "2_2") (pintype "passive"))
      (node (ref "R8") (pin "1") (pinfunction "1_1") (pintype "passive"))
      (node (ref "U$2") (pin "AA2") (pinfunction "1_AA2") (pintype "bidirectional"))
      (node (ref "U$2") (pin "BA2") (pinfunction "1_BA2") (pintype "bidirectional"))
    )
    (net (code "97") (name "unconnected-(E6B-~{Q}-Pad8)") (class "Default")
      (node (ref "E6") (pin "8") (pinfunction "~{Q}_8") (pintype "output"))
    )
    (net (code "98") (name "unconnected-(E16A-Q-Pad5)") (class "Default")
      (node (ref "E16") (pin "5") (pinfunction "Q_5") (pintype "output"))
    )
    (net (code "99") (name "unconnected-(E18A-O-Pad3)") (class "Default")
      (node (ref "E18") (pin "3") (pinfunction "O_3") (pintype "output"))
    )
    (net (code "100") (name "unconnected-(E18B-O-Pad6)") (class "Default")
      (node (ref "E18") (pin "6") (pinfunction "O_6") (pintype "output"))
    )
  )
)
